# Powermodule.net
KiCad netlist of a schematic drawn in EAGLE
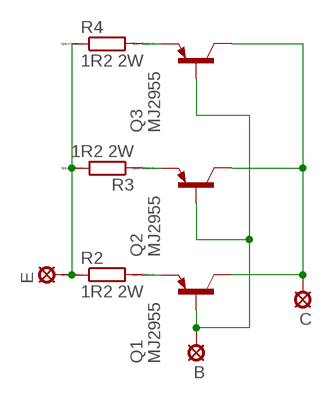
[diagram p0: schematic, sheet 1]

(export (version "E")
  (design (tool "Eeschema 10.0.6"))
  (components
    (comp (ref "B")
      (value "SE14")
      (footprint "eagle-import:SE14")
      (libsource (lib "eagle-import") (part "SE14"))
    )
    (comp (ref "C")
      (value "SE14")
      (footprint "eagle-import:SE14")
      (libsource (lib "eagle-import") (part "SE14"))
    )
    (comp (ref "E")
      (value "SE14")
      (footprint "eagle-import:SE14")
      (libsource (lib "eagle-import") (part "SE14"))
    )
    (comp (ref "Q1")
      (value "MJ2955")
      (footprint "eagle-import:TO3")
      (libsource (lib "eagle-import") (part "MJ2955"))
    )
    (comp (ref "Q2")
      (value "MJ2955")
      (footprint "eagle-import:TO3")
      (libsource (lib "eagle-import") (part "MJ2955"))
    )
    (comp (ref "Q3")
      (value "MJ2955")
      (footprint "eagle-import:TO3")
      (libsource (lib "eagle-import") (part "MJ2955"))
    )
    (comp (ref "R2")
      (value "1R2 2W")
      (footprint "eagle-import:0207_10")
      (libsource (lib "eagle-import") (part "R0207/10"))
    )
    (comp (ref "R3")
      (value "1R2 2W")
      (footprint "eagle-import:0207_10")
      (libsource (lib "eagle-import") (part "R0207/10"))
    )
    (comp (ref "R4")
      (value "1R2 2W")
      (footprint "eagle-import:0207_10")
      (libsource (lib "eagle-import") (part "R0207/10"))
    )
  )
  (nets
    (net (code "1") (name "Net-(B-PadMP)") (class "Default")
      (node (ref "B") (pin "MP") (pinfunction "MP_MP") (pintype "passive"))
      (node (ref "Q1") (pin "B") (pinfunction "B_B") (pintype "passive"))
      (node (ref "Q2") (pin "B") (pinfunction "B_B") (pintype "passive"))
      (node (ref "Q3") (pin "B") (pinfunction "B_B") (pintype "passive"))
    )
    (net (code "2") (name "Net-(C-PadMP)") (class "Default")
      (node (ref "C") (pin "MP") (pinfunction "MP_MP") (pintype "passive"))
      (node (ref "Q1") (pin "C") (pinfunction "C_C") (pintype "passive"))
      (node (ref "Q1") (pin "C/") (pinfunction "C_C/") (pintype "passive"))
      (node (ref "Q2") (pin "C") (pinfunction "C_C") (pintype "passive"))
      (node (ref "Q2") (pin "C/") (pinfunction "C_C/") (pintype "passive"))
      (node (ref "Q3") (pin "C") (pinfunction "C_C") (pintype "passive"))
      (node (ref "Q3") (pin "C/") (pinfunction "C_C/") (pintype "passive"))
    )
    (net (code "3") (name "Net-(E-PadMP)") (class "Default")
      (node (ref "E") (pin "MP") (pinfunction "MP_MP") (pintype "passive"))
      (node (ref "R2") (pin "1") (pinfunction "1_1") (pintype "passive"))
      (node (ref "R3") (pin "2") (pinfunction "2_2") (pintype "passive"))
      (node (ref "R4") (pin "1") (pinfunction "1_1") (pintype "passive"))
    )
    (net (code "4") (name "Net-(Q1-PadE)") (class "Default")
      (node (ref "Q1") (pin "E") (pinfunction "E_E") (pintype "passive"))
      (node (ref "R2") (pin "2") (pinfunction "2_2") (pintype "passive"))
    )
    (net (code "5") (name "Net-(Q2-PadE)") (class "Default")
      (node (ref "Q2") (pin "E") (pinfunction "E_E") (pintype "passive"))
      (node (ref "R3") (pin "1") (pinfunction "1_1") (pintype "passive"))
    )
    (net (code "6") (name "Net-(Q3-PadE)") (class "Default")
      (node (ref "Q3") (pin "E") (pinfunction "E_E") (pintype "passive"))
      (node (ref "R4") (pin "2") (pinfunction "2_2") (pintype "passive"))
    )
  )
)
